# Allproject.net
KiCad netlist of a schematic drawn in Altium Designer
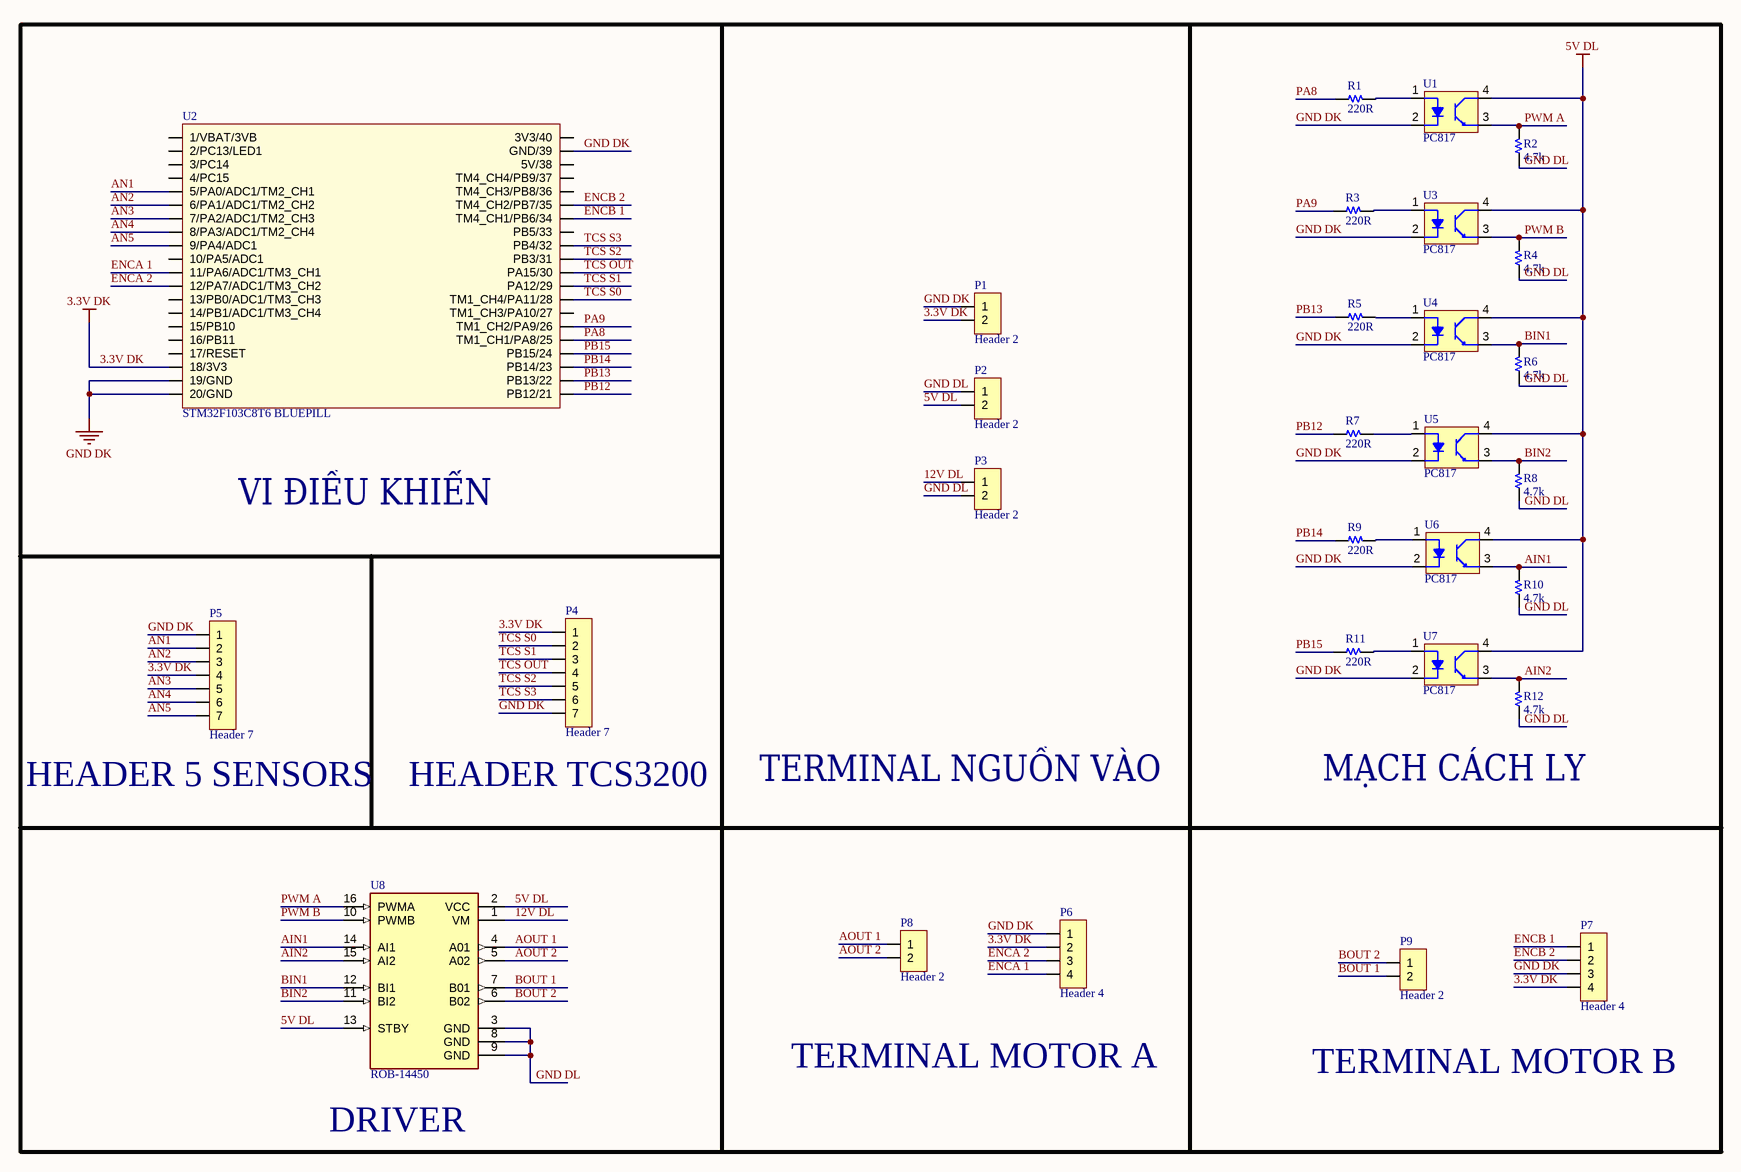
[diagram p0: Allproject.SchDoc]

(export (version "E")
  (design (tool "Eeschema 10.0.6"))
  (components
    (comp (ref "P1")
      (value "Header 2")
      (footprint "HDR/Terminal/2")
      (description "Header, 2-Pin")
      (libsource (lib "chipfc_altium_libs") (part "Header 2"))
    )
    (comp (ref "P2")
      (value "Header 2")
      (footprint "HDR/Terminal/2")
      (description "Header, 2-Pin")
      (libsource (lib "chipfc_altium_libs") (part "Header 2"))
    )
    (comp (ref "P3")
      (value "Header 2")
      (footprint "HDR/Terminal/2")
      (description "Header, 2-Pin")
      (libsource (lib "chipfc_altium_libs") (part "Header 2"))
    )
    (comp (ref "P4")
      (value "Header 7")
      (footprint "HDR/Header/7")
      (description "Header, 7-Pin")
      (libsource (lib "chipfc_altium_libs") (part "Header 7"))
    )
    (comp (ref "P5")
      (value "Header 7")
      (footprint "HDR/Header/7")
      (description "Header, 7-Pin")
      (libsource (lib "chipfc_altium_libs") (part "Header 7"))
    )
    (comp (ref "P6")
      (value "Header 4")
      (footprint "HDR/Terminal/4")
      (description "Header, 4-Pin")
      (libsource (lib "chipfc_altium_libs") (part "Header 4"))
    )
    (comp (ref "P7")
      (value "Header 4")
      (footprint "HDR/Terminal/4")
      (description "Header, 4-Pin")
      (libsource (lib "chipfc_altium_libs") (part "Header 4"))
    )
    (comp (ref "P8")
      (value "Header 2")
      (footprint "HDR/Terminal/2")
      (description "Header, 2-Pin")
      (libsource (lib "chipfc_altium_libs") (part "Header 2"))
    )
    (comp (ref "P9")
      (value "Header 2")
      (footprint "HDR/Terminal/2")
      (description "Header, 2-Pin")
      (libsource (lib "chipfc_altium_libs") (part "Header 2"))
    )
    (comp (ref "R1")
      (value "220R")
      (footprint "R 1/4W/300")
      (description "Resistor")
      (libsource (lib "chipfc_altium_libs") (part "Resistor"))
    )
    (comp (ref "R2")
      (value "4.7k")
      (footprint "R 1/4W/300")
      (description "Resistor")
      (libsource (lib "chipfc_altium_libs") (part "Resistor"))
    )
    (comp (ref "R3")
      (value "220R")
      (footprint "R 1/4W/300")
      (description "Resistor")
      (libsource (lib "chipfc_altium_libs") (part "Resistor"))
    )
    (comp (ref "R4")
      (value "4.7k")
      (footprint "R 1/4W/300")
      (description "Resistor")
      (libsource (lib "chipfc_altium_libs") (part "Resistor"))
    )
    (comp (ref "R5")
      (value "220R")
      (footprint "R 1/4W/300")
      (description "Resistor")
      (libsource (lib "chipfc_altium_libs") (part "Resistor"))
    )
    (comp (ref "R6")
      (value "4.7k")
      (footprint "R 1/4W/300")
      (description "Resistor")
      (libsource (lib "chipfc_altium_libs") (part "Resistor"))
    )
    (comp (ref "R7")
      (value "220R")
      (footprint "R 1/4W/300")
      (description "Resistor")
      (libsource (lib "chipfc_altium_libs") (part "Resistor"))
    )
    (comp (ref "R8")
      (value "4.7k")
      (footprint "R 1/4W/300")
      (description "Resistor")
      (libsource (lib "chipfc_altium_libs") (part "Resistor"))
    )
    (comp (ref "R9")
      (value "220R")
      (footprint "R 1/4W/300")
      (description "Resistor")
      (libsource (lib "chipfc_altium_libs") (part "Resistor"))
    )
    (comp (ref "R10")
      (value "4.7k")
      (footprint "R 1/4W/300")
      (description "Resistor")
      (libsource (lib "chipfc_altium_libs") (part "Resistor"))
    )
    (comp (ref "R11")
      (value "220R")
      (footprint "R 1/4W/300")
      (description "Resistor")
      (libsource (lib "chipfc_altium_libs") (part "Resistor"))
    )
    (comp (ref "R12")
      (value "4.7k")
      (footprint "R 1/4W/300")
      (description "Resistor")
      (libsource (lib "chipfc_altium_libs") (part "Resistor"))
    )
    (comp (ref "U1")
      (value "PC817")
      (footprint "DIP4 - PC817")
      (description "Opto PC817B")
      (libsource (lib "chipfc_altium_libs") (part "PC817"))
    )
    (comp (ref "U2")
      (value "STM32F103C8T6 BLUEPILL")
      (footprint "Female header 20x20 pin")
      (description "Connector 9")
      (libsource (lib "NGHIA") (part "STM32F103C8T6 KIT BLUE PILL"))
    )
    (comp (ref "U3")
      (value "PC817")
      (footprint "DIP4 - PC817")
      (description "Opto PC817B")
      (libsource (lib "chipfc_altium_libs") (part "PC817"))
    )
    (comp (ref "U4")
      (value "PC817")
      (footprint "DIP4 - PC817")
      (description "Opto PC817B")
      (libsource (lib "chipfc_altium_libs") (part "PC817"))
    )
    (comp (ref "U5")
      (value "PC817")
      (footprint "DIP4 - PC817")
      (description "Opto PC817B")
      (libsource (lib "chipfc_altium_libs") (part "PC817"))
    )
    (comp (ref "U6")
      (value "PC817")
      (footprint "DIP4 - PC817")
      (description "Opto PC817B")
      (libsource (lib "chipfc_altium_libs") (part "PC817"))
    )
    (comp (ref "U7")
      (value "PC817")
      (footprint "DIP4 - PC817")
      (description "Opto PC817B")
      (libsource (lib "chipfc_altium_libs") (part "PC817"))
    )
    (comp (ref "U8")
      (value "ROB-14450")
      (footprint "MODULE_ROB-14450")
      (description "TB6612FNG Motor Controller/Driver Power Management Evaluation Board")
      (fields (field (name "MF") "SparkFun Electronics"))
      (libsource (lib "ROB-14450") (part "ROB-14450"))
    )
  )
  (nets
    (net (code "1") (name "/12V DL") (class "Default")
      (node (ref "P3") (pin "1") (pinfunction "1_1") (pintype "passive"))
      (node (ref "U8") (pin "1") (pinfunction "VM_1") (pintype "power_in"))
    )
    (net (code "2") (name "/AIN1") (class "Default")
      (node (ref "R10") (pin "2") (pinfunction "2_2") (pintype "passive"))
      (node (ref "U6") (pin "3") (pinfunction "E_3") (pintype "passive"))
      (node (ref "U8") (pin "14") (pinfunction "AI1_14") (pintype "input"))
    )
    (net (code "3") (name "/AIN2") (class "Default")
      (node (ref "R12") (pin "2") (pinfunction "2_2") (pintype "passive"))
      (node (ref "U7") (pin "3") (pinfunction "E_3") (pintype "passive"))
      (node (ref "U8") (pin "15") (pinfunction "AI2_15") (pintype "input"))
    )
    (net (code "4") (name "/AN1") (class "Default")
      (node (ref "P5") (pin "2") (pinfunction "2_2") (pintype "passive"))
      (node (ref "U2") (pin "5") (pinfunction "5/PA0/ADC1/TM2_CH1_5") (pintype "passive"))
    )
    (net (code "5") (name "/AN2") (class "Default")
      (node (ref "P5") (pin "3") (pinfunction "3_3") (pintype "passive"))
      (node (ref "U2") (pin "6") (pinfunction "6/PA1/ADC1/TM2_CH2_6") (pintype "passive"))
    )
    (net (code "6") (name "/AN3") (class "Default")
      (node (ref "P5") (pin "5") (pinfunction "5_5") (pintype "passive"))
      (node (ref "U2") (pin "7") (pinfunction "7/PA2/ADC1/TM2_CH3_7") (pintype "passive"))
    )
    (net (code "7") (name "/AN4") (class "Default")
      (node (ref "P5") (pin "6") (pinfunction "6_6") (pintype "passive"))
      (node (ref "U2") (pin "8") (pinfunction "8/PA3/ADC1/TM2_CH4_8") (pintype "passive"))
    )
    (net (code "8") (name "/AN5") (class "Default")
      (node (ref "P5") (pin "7") (pinfunction "7_7") (pintype "passive"))
      (node (ref "U2") (pin "9") (pinfunction "9/PA4/ADC1_9") (pintype "passive"))
    )
    (net (code "9") (name "/AOUT 1") (class "Default")
      (node (ref "P8") (pin "1") (pinfunction "1_1") (pintype "passive"))
      (node (ref "U8") (pin "4") (pinfunction "A01_4") (pintype "output"))
    )
    (net (code "10") (name "/AOUT 2") (class "Default")
      (node (ref "P8") (pin "2") (pinfunction "2_2") (pintype "passive"))
      (node (ref "U8") (pin "5") (pinfunction "A02_5") (pintype "output"))
    )
    (net (code "11") (name "/BIN1") (class "Default")
      (node (ref "R6") (pin "2") (pinfunction "2_2") (pintype "passive"))
      (node (ref "U4") (pin "3") (pinfunction "E_3") (pintype "passive"))
      (node (ref "U8") (pin "12") (pinfunction "BI1_12") (pintype "input"))
    )
    (net (code "12") (name "/BIN2") (class "Default")
      (node (ref "R8") (pin "2") (pinfunction "2_2") (pintype "passive"))
      (node (ref "U5") (pin "3") (pinfunction "E_3") (pintype "passive"))
      (node (ref "U8") (pin "11") (pinfunction "BI2_11") (pintype "input"))
    )
    (net (code "13") (name "/BOUT 1") (class "Default")
      (node (ref "P9") (pin "2") (pinfunction "2_2") (pintype "passive"))
      (node (ref "U8") (pin "7") (pinfunction "B01_7") (pintype "output"))
    )
    (net (code "14") (name "/BOUT 2") (class "Default")
      (node (ref "P9") (pin "1") (pinfunction "1_1") (pintype "passive"))
      (node (ref "U8") (pin "6") (pinfunction "B02_6") (pintype "output"))
    )
    (net (code "15") (name "/ENCA 1") (class "Default")
      (node (ref "P6") (pin "4") (pinfunction "4_4") (pintype "passive"))
      (node (ref "U2") (pin "11") (pinfunction "11/PA6/ADC1/TM3_CH1_11") (pintype "passive"))
    )
    (net (code "16") (name "/ENCA 2") (class "Default")
      (node (ref "P6") (pin "3") (pinfunction "3_3") (pintype "passive"))
      (node (ref "U2") (pin "12") (pinfunction "12/PA7/ADC1/TM3_CH2_12") (pintype "passive"))
    )
    (net (code "17") (name "/ENCB 1") (class "Default")
      (node (ref "P7") (pin "1") (pinfunction "1_1") (pintype "passive"))
      (node (ref "U2") (pin "34") (pinfunction "TM4_CH1/PB6/34_34") (pintype "passive"))
    )
    (net (code "18") (name "/ENCB 2") (class "Default")
      (node (ref "P7") (pin "2") (pinfunction "2_2") (pintype "passive"))
      (node (ref "U2") (pin "35") (pinfunction "TM4_CH2/PB7/35_35") (pintype "passive"))
    )
    (net (code "19") (name "/GND DL") (class "Default")
      (node (ref "P2") (pin "1") (pinfunction "1_1") (pintype "passive"))
      (node (ref "P3") (pin "2") (pinfunction "2_2") (pintype "passive"))
      (node (ref "R10") (pin "1") (pinfunction "1_1") (pintype "passive"))
      (node (ref "R12") (pin "1") (pinfunction "1_1") (pintype "passive"))
      (node (ref "R2") (pin "1") (pinfunction "1_1") (pintype "passive"))
      (node (ref "R4") (pin "1") (pinfunction "1_1") (pintype "passive"))
      (node (ref "R6") (pin "1") (pinfunction "1_1") (pintype "passive"))
      (node (ref "R8") (pin "1") (pinfunction "1_1") (pintype "passive"))
      (node (ref "U8") (pin "3") (pinfunction "GND_3") (pintype "power_in"))
      (node (ref "U8") (pin "8") (pinfunction "GND_8") (pintype "power_in"))
      (node (ref "U8") (pin "9") (pinfunction "GND_9") (pintype "power_in"))
    )
    (net (code "20") (name "/PA8") (class "Default")
      (node (ref "R1") (pin "1") (pinfunction "1_1") (pintype "passive"))
      (node (ref "U2") (pin "25") (pinfunction "TM1_CH1/PA8/25_25") (pintype "passive"))
    )
    (net (code "21") (name "/PA9") (class "Default")
      (node (ref "R3") (pin "1") (pinfunction "1_1") (pintype "passive"))
      (node (ref "U2") (pin "26") (pinfunction "TM1_CH2/PA9/26_26") (pintype "passive"))
    )
    (net (code "22") (name "/PB12") (class "Default")
      (node (ref "R7") (pin "1") (pinfunction "1_1") (pintype "passive"))
      (node (ref "U2") (pin "21") (pinfunction "PB12/21_21") (pintype "passive"))
    )
    (net (code "23") (name "/PB13") (class "Default")
      (node (ref "R5") (pin "1") (pinfunction "1_1") (pintype "passive"))
      (node (ref "U2") (pin "22") (pinfunction "PB13/22_22") (pintype "passive"))
    )
    (net (code "24") (name "/PB14") (class "Default")
      (node (ref "R9") (pin "1") (pinfunction "1_1") (pintype "passive"))
      (node (ref "U2") (pin "23") (pinfunction "PB14/23_23") (pintype "passive"))
    )
    (net (code "25") (name "/PB15") (class "Default")
      (node (ref "R11") (pin "1") (pinfunction "1_1") (pintype "passive"))
      (node (ref "U2") (pin "24") (pinfunction "PB15/24_24") (pintype "passive"))
    )
    (net (code "26") (name "/PWM A") (class "Default")
      (node (ref "R2") (pin "2") (pinfunction "2_2") (pintype "passive"))
      (node (ref "U1") (pin "3") (pinfunction "E_3") (pintype "passive"))
      (node (ref "U8") (pin "16") (pinfunction "PWMA_16") (pintype "input"))
    )
    (net (code "27") (name "/PWM B") (class "Default")
      (node (ref "R4") (pin "2") (pinfunction "2_2") (pintype "passive"))
      (node (ref "U3") (pin "3") (pinfunction "E_3") (pintype "passive"))
      (node (ref "U8") (pin "10") (pinfunction "PWMB_10") (pintype "input"))
    )
    (net (code "28") (name "/TCS OUT") (class "Default")
      (node (ref "P4") (pin "4") (pinfunction "4_4") (pintype "passive"))
      (node (ref "U2") (pin "30") (pinfunction "PA15/30_30") (pintype "passive"))
    )
    (net (code "29") (name "/TCS S0") (class "Default")
      (node (ref "P4") (pin "2") (pinfunction "2_2") (pintype "passive"))
      (node (ref "U2") (pin "28") (pinfunction "TM1_CH4/PA11/28_28") (pintype "passive"))
    )
    (net (code "30") (name "/TCS S1") (class "Default")
      (node (ref "P4") (pin "3") (pinfunction "3_3") (pintype "passive"))
      (node (ref "U2") (pin "29") (pinfunction "PA12/29_29") (pintype "passive"))
    )
    (net (code "31") (name "/TCS S2") (class "Default")
      (node (ref "P4") (pin "5") (pinfunction "5_5") (pintype "passive"))
      (node (ref "U2") (pin "31") (pinfunction "PB3/31_31") (pintype "passive"))
    )
    (net (code "32") (name "/TCS S3") (class "Default")
      (node (ref "P4") (pin "6") (pinfunction "6_6") (pintype "passive"))
      (node (ref "U2") (pin "32") (pinfunction "PB4/32_32") (pintype "passive"))
    )
    (net (code "33") (name "3.3V DK") (class "Default")
      (node (ref "P1") (pin "2") (pinfunction "2_2") (pintype "passive"))
      (node (ref "P4") (pin "1") (pinfunction "1_1") (pintype "passive"))
      (node (ref "P5") (pin "4") (pinfunction "4_4") (pintype "passive"))
      (node (ref "P6") (pin "2") (pinfunction "2_2") (pintype "passive"))
      (node (ref "P7") (pin "4") (pinfunction "4_4") (pintype "passive"))
      (node (ref "U2") (pin "18") (pinfunction "18/3V3_18") (pintype "passive"))
    )
    (net (code "34") (name "5V DL") (class "Default")
      (node (ref "P2") (pin "2") (pinfunction "2_2") (pintype "passive"))
      (node (ref "U1") (pin "4") (pinfunction "C_4") (pintype "passive"))
      (node (ref "U3") (pin "4") (pinfunction "C_4") (pintype "passive"))
      (node (ref "U4") (pin "4") (pinfunction "C_4") (pintype "passive"))
      (node (ref "U5") (pin "4") (pinfunction "C_4") (pintype "passive"))
      (node (ref "U6") (pin "4") (pinfunction "C_4") (pintype "passive"))
      (node (ref "U7") (pin "4") (pinfunction "C_4") (pintype "passive"))
      (node (ref "U8") (pin "13") (pinfunction "STBY_13") (pintype "input"))
      (node (ref "U8") (pin "2") (pinfunction "VCC_2") (pintype "power_in"))
    )
    (net (code "35") (name "GND DK") (class "Default")
      (node (ref "P1") (pin "1") (pinfunction "1_1") (pintype "passive"))
      (node (ref "P4") (pin "7") (pinfunction "7_7") (pintype "passive"))
      (node (ref "P5") (pin "1") (pinfunction "1_1") (pintype "passive"))
      (node (ref "P6") (pin "1") (pinfunction "1_1") (pintype "passive"))
      (node (ref "P7") (pin "3") (pinfunction "3_3") (pintype "passive"))
      (node (ref "U1") (pin "2") (pinfunction "K_2") (pintype "passive"))
      (node (ref "U2") (pin "19") (pinfunction "19/GND_19") (pintype "passive"))
      (node (ref "U2") (pin "20") (pinfunction "20/GND_20") (pintype "passive"))
      (node (ref "U2") (pin "39") (pinfunction "GND/39_39") (pintype "passive"))
      (node (ref "U3") (pin "2") (pinfunction "K_2") (pintype "passive"))
      (node (ref "U4") (pin "2") (pinfunction "K_2") (pintype "passive"))
      (node (ref "U5") (pin "2") (pinfunction "K_2") (pintype "passive"))
      (node (ref "U6") (pin "2") (pinfunction "K_2") (pintype "passive"))
      (node (ref "U7") (pin "2") (pinfunction "K_2") (pintype "passive"))
    )
    (net (code "36") (name "Net-(U1-A)") (class "Default")
      (node (ref "R1") (pin "2") (pinfunction "2_2") (pintype "passive"))
      (node (ref "U1") (pin "1") (pinfunction "A_1") (pintype "passive"))
    )
    (net (code "37") (name "Net-(U3-A)") (class "Default")
      (node (ref "R3") (pin "2") (pinfunction "2_2") (pintype "passive"))
      (node (ref "U3") (pin "1") (pinfunction "A_1") (pintype "passive"))
    )
    (net (code "38") (name "Net-(U4-A)") (class "Default")
      (node (ref "R5") (pin "2") (pinfunction "2_2") (pintype "passive"))
      (node (ref "U4") (pin "1") (pinfunction "A_1") (pintype "passive"))
    )
    (net (code "39") (name "Net-(U5-A)") (class "Default")
      (node (ref "R7") (pin "2") (pinfunction "2_2") (pintype "passive"))
      (node (ref "U5") (pin "1") (pinfunction "A_1") (pintype "passive"))
    )
    (net (code "40") (name "Net-(U6-A)") (class "Default")
      (node (ref "R9") (pin "2") (pinfunction "2_2") (pintype "passive"))
      (node (ref "U6") (pin "1") (pinfunction "A_1") (pintype "passive"))
    )
    (net (code "41") (name "Net-(U7-A)") (class "Default")
      (node (ref "R11") (pin "2") (pinfunction "2_2") (pintype "passive"))
      (node (ref "U7") (pin "1") (pinfunction "A_1") (pintype "passive"))
    )
    (net (code "42") (name "unconnected-(U2-1{slash}VBAT{slash}3VB-Pad1)") (class "Default")
      (node (ref "U2") (pin "1") (pinfunction "1/VBAT/3VB_1") (pintype "passive"))
    )
    (net (code "43") (name "unconnected-(U2-2{slash}PC13{slash}LED1-Pad2)") (class "Default")
      (node (ref "U2") (pin "2") (pinfunction "2/PC13/LED1_2") (pintype "passive"))
    )
    (net (code "44") (name "unconnected-(U2-3V3{slash}40-Pad40)") (class "Default")
      (node (ref "U2") (pin "40") (pinfunction "3V3/40_40") (pintype "passive"))
    )
    (net (code "45") (name "unconnected-(U2-3{slash}PC14-Pad3)") (class "Default")
      (node (ref "U2") (pin "3") (pinfunction "3/PC14_3") (pintype "passive"))
    )
    (net (code "46") (name "unconnected-(U2-4{slash}PC15-Pad4)") (class "Default")
      (node (ref "U2") (pin "4") (pinfunction "4/PC15_4") (pintype "passive"))
    )
    (net (code "47") (name "unconnected-(U2-5V{slash}38-Pad38)") (class "Default")
      (node (ref "U2") (pin "38") (pinfunction "5V/38_38") (pintype "passive"))
    )
    (net (code "48") (name "unconnected-(U2-10{slash}PA5{slash}ADC1-Pad10)") (class "Default")
      (node (ref "U2") (pin "10") (pinfunction "10/PA5/ADC1_10") (pintype "passive"))
    )
    (net (code "49") (name "unconnected-(U2-13{slash}PB0{slash}ADC1{slash}TM3_CH3-Pad13)") (class "Default")
      (node (ref "U2") (pin "13") (pinfunction "13/PB0/ADC1/TM3_CH3_13") (pintype "passive"))
    )
    (net (code "50") (name "unconnected-(U2-14{slash}PB1{slash}ADC1{slash}TM3_CH4-Pad14)") (class "Default")
      (node (ref "U2") (pin "14") (pinfunction "14/PB1/ADC1/TM3_CH4_14") (pintype "passive"))
    )
    (net (code "51") (name "unconnected-(U2-15{slash}PB10-Pad15)") (class "Default")
      (node (ref "U2") (pin "15") (pinfunction "15/PB10_15") (pintype "passive"))
    )
    (net (code "52") (name "unconnected-(U2-16{slash}PB11-Pad16)") (class "Default")
      (node (ref "U2") (pin "16") (pinfunction "16/PB11_16") (pintype "passive"))
    )
    (net (code "53") (name "unconnected-(U2-17{slash}RESET-Pad17)") (class "Default")
      (node (ref "U2") (pin "17") (pinfunction "17/RESET_17") (pintype "passive"))
    )
    (net (code "54") (name "unconnected-(U2-PB5{slash}33-Pad33)") (class "Default")
      (node (ref "U2") (pin "33") (pinfunction "PB5/33_33") (pintype "passive"))
    )
    (net (code "55") (name "unconnected-(U2-TM1_CH3{slash}PA10{slash}27-Pad27)") (class "Default")
      (node (ref "U2") (pin "27") (pinfunction "TM1_CH3/PA10/27_27") (pintype "passive"))
    )
    (net (code "56") (name "unconnected-(U2-TM4_CH3{slash}PB8{slash}36-Pad36)") (class "Default")
      (node (ref "U2") (pin "36") (pinfunction "TM4_CH3/PB8/36_36") (pintype "passive"))
    )
    (net (code "57") (name "unconnected-(U2-TM4_CH4{slash}PB9{slash}37-Pad37)") (class "Default")
      (node (ref "U2") (pin "37") (pinfunction "TM4_CH4/PB9/37_37") (pintype "passive"))
    )
  )
)
